# audio-amp-v1.net
KiCad netlist of a schematic drawn in EAGLE
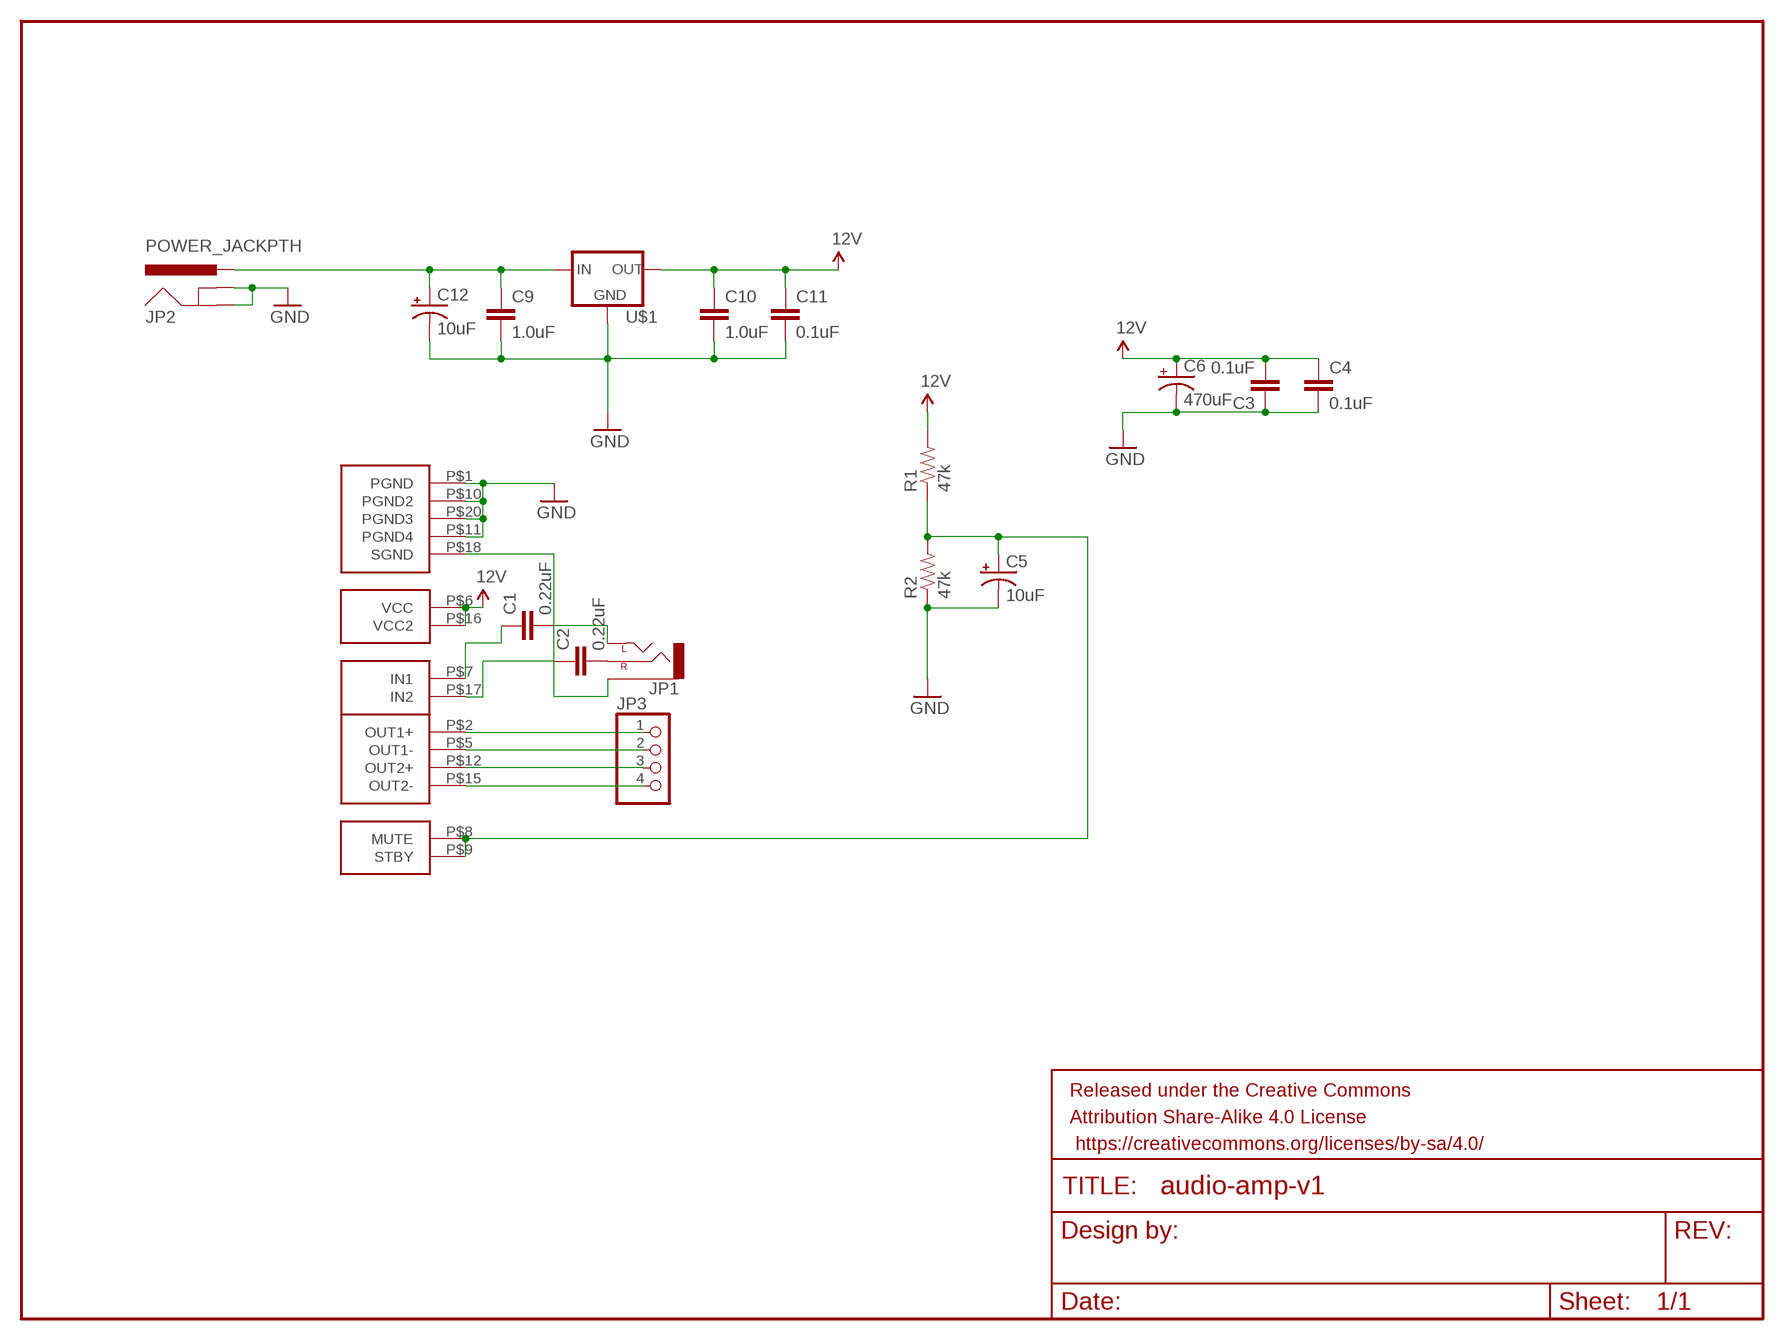
[diagram p0: schematic, sheet 1]

(export (version "E")
  (design (tool "Eeschema 10.0.6"))
  (components
    (comp (ref "C1")
      (value "0.22uF")
      (footprint "eagle-import:0603-CAP")
      (libsource (lib "eagle-import") (part "0.22UF-25V-10%(0603)"))
    )
    (comp (ref "C2")
      (value "0.22uF")
      (footprint "eagle-import:0603-CAP")
      (libsource (lib "eagle-import") (part "0.22UF-25V-10%(0603)"))
    )
    (comp (ref "C3")
      (value "0.1uF")
      (footprint "eagle-import:0603-CAP")
      (libsource (lib "eagle-import") (part "0.1UF-25V-5%(0603)"))
    )
    (comp (ref "C4")
      (value "0.1uF")
      (footprint "eagle-import:0603-CAP")
      (libsource (lib "eagle-import") (part "0.1UF-25V-5%(0603)"))
    )
    (comp (ref "C5")
      (value "10uF")
      (footprint "eagle-import:PANASONIC_C")
      (libsource (lib "eagle-import") (part "CAP_POLC"))
    )
    (comp (ref "C6")
      (value "470uF")
      (footprint "eagle-import:NIC_10X10.5_CAP")
      (libsource (lib "eagle-import") (part "100UF-63V-20%(ELECT)"))
    )
    (comp (ref "C9")
      (value "1.0uF")
      (footprint "eagle-import:0603-CAP")
      (libsource (lib "eagle-import") (part "1.0UF-16V-10%(0603)"))
    )
    (comp (ref "C10")
      (value "1.0uF")
      (footprint "eagle-import:0603-CAP")
      (libsource (lib "eagle-import") (part "1.0UF-16V-10%(0603)"))
    )
    (comp (ref "C11")
      (value "0.1uF")
      (footprint "eagle-import:0603-CAP")
      (libsource (lib "eagle-import") (part "1.0UF-16V-10%(0603)"))
    )
    (comp (ref "C12")
      (value "10uF")
      (footprint "eagle-import:PANASONIC_C")
      (libsource (lib "eagle-import") (part "CAP_POLC"))
    )
    (comp (ref "FRAME1")
      (value "FRAME-LETTERNO_PACKAGE")
      (footprint "eagle-import:DUMMY")
      (fields (field (name "DESIGNER") "Nobody"))
      (libsource (lib "eagle-import") (part "FRAME-LETTERNO_PACKAGE"))
    )
    (comp (ref "JP1")
      (value "AUDIO-JACKSMD2")
      (footprint "eagle-import:AUDIO-JACK-3.5MM-SMD")
      (libsource (lib "eagle-import") (part "AUDIO-JACKSMD2"))
    )
    (comp (ref "JP2")
      (value "POWER_JACKPTH")
      (footprint "eagle-import:POWER_JACK_PTH")
      (libsource (lib "eagle-import") (part "POWER_JACKPTH"))
    )
    (comp (ref "JP3")
      (value "PINHD-1X4")
      (footprint "eagle-import:1X04")
      (libsource (lib "eagle-import") (part "PINHD-1X4"))
    )
    (comp (ref "R1")
      (value "47k")
      (footprint "eagle-import:0603-RES")
      (libsource (lib "eagle-import") (part "RESISTOR0603-RES"))
    )
    (comp (ref "R2")
      (value "47k")
      (footprint "eagle-import:0603-RES")
      (libsource (lib "eagle-import") (part "RESISTOR0603-RES"))
    )
    (comp (ref "U$1")
      (value "V_REG_78XX-TO-220")
      (footprint "eagle-import:TO-220-ALT")
      (libsource (lib "eagle-import") (part "V_REG_78XX-TO-220"))
    )
    (comp (ref "U$2")
      (value "TDA7266D")
      (footprint "eagle-import:TDA7266D")
      (libsource (lib "eagle-import") (part "TDA7266D"))
    )
  )
  (nets
    (net (code "1") (name "12V") (class "Default")
      (node (ref "C10") (pin "1") (pinfunction "1_1") (pintype "passive"))
      (node (ref "C11") (pin "1") (pinfunction "1_1") (pintype "passive"))
      (node (ref "C3") (pin "2") (pinfunction "2_2") (pintype "passive"))
      (node (ref "C4") (pin "1") (pinfunction "1_1") (pintype "passive"))
      (node (ref "C6") (pin "+") (pinfunction "+_+") (pintype "passive"))
      (node (ref "R1") (pin "2") (pinfunction "2_2") (pintype "passive"))
      (node (ref "U$1") (pin "OUT") (pinfunction "OUT_OUT") (pintype "passive"))
      (node (ref "U$2") (pin "P$16") (pinfunction "VCC2_P$16") (pintype "bidirectional"))
      (node (ref "U$2") (pin "P$6") (pinfunction "VCC_P$6") (pintype "bidirectional"))
    )
    (net (code "2") (name "GND") (class "Default")
      (node (ref "C10") (pin "2") (pinfunction "2_2") (pintype "passive"))
      (node (ref "C11") (pin "2") (pinfunction "2_2") (pintype "passive"))
      (node (ref "C12") (pin "-") (pinfunction "-_-") (pintype "passive"))
      (node (ref "C3") (pin "1") (pinfunction "1_1") (pintype "passive"))
      (node (ref "C4") (pin "2") (pinfunction "2_2") (pintype "passive"))
      (node (ref "C5") (pin "-") (pinfunction "-_-") (pintype "passive"))
      (node (ref "C6") (pin "-") (pinfunction "-_-") (pintype "passive"))
      (node (ref "C9") (pin "2") (pinfunction "2_2") (pintype "passive"))
      (node (ref "JP2") (pin "GND") (pinfunction "GND_GND") (pintype "bidirectional"))
      (node (ref "JP2") (pin "GNDBREAK") (pinfunction "GNDBREAK_GNDBREAK") (pintype "bidirectional"))
      (node (ref "R2") (pin "1") (pinfunction "1_1") (pintype "passive"))
      (node (ref "U$1") (pin "GND") (pinfunction "GND_GND") (pintype "input"))
      (node (ref "U$2") (pin "P$1") (pinfunction "PGND_P$1") (pintype "bidirectional"))
      (node (ref "U$2") (pin "P$10") (pinfunction "PGND2_P$10") (pintype "bidirectional"))
      (node (ref "U$2") (pin "P$11") (pinfunction "PGND4_P$11") (pintype "bidirectional"))
      (node (ref "U$2") (pin "P$20") (pinfunction "PGND3_P$20") (pintype "bidirectional"))
    )
    (net (code "3") (name "Net-(C12-Pad+)") (class "Default")
      (node (ref "C12") (pin "+") (pinfunction "+_+") (pintype "passive"))
      (node (ref "C9") (pin "1") (pinfunction "1_1") (pintype "passive"))
      (node (ref "JP2") (pin "PWR") (pinfunction "PWR_PWR") (pintype "bidirectional"))
      (node (ref "U$1") (pin "IN") (pinfunction "IN_IN") (pintype "input"))
    )
    (net (code "4") (name "Net-(JP1-LEFT)") (class "Default")
      (node (ref "C1") (pin "2") (pinfunction "2_2") (pintype "passive"))
      (node (ref "JP1") (pin "TIP") (pinfunction "LEFT_TIP") (pintype "bidirectional"))
    )
    (net (code "5") (name "Net-(JP1-RIGHT)") (class "Default")
      (node (ref "C2") (pin "2") (pinfunction "2_2") (pintype "passive"))
      (node (ref "JP1") (pin "RING") (pinfunction "RIGHT_RING") (pintype "bidirectional"))
    )
    (net (code "6") (name "Net-(U$2-IN1)") (class "Default")
      (node (ref "C1") (pin "1") (pinfunction "1_1") (pintype "passive"))
      (node (ref "U$2") (pin "P$7") (pinfunction "IN1_P$7") (pintype "bidirectional"))
    )
    (net (code "7") (name "Net-(U$2-IN2)") (class "Default")
      (node (ref "C2") (pin "1") (pinfunction "1_1") (pintype "passive"))
      (node (ref "U$2") (pin "P$17") (pinfunction "IN2_P$17") (pintype "bidirectional"))
    )
    (net (code "8") (name "Net-(U$2-MUTE)") (class "Default")
      (node (ref "C5") (pin "+") (pinfunction "+_+") (pintype "passive"))
      (node (ref "R1") (pin "1") (pinfunction "1_1") (pintype "passive"))
      (node (ref "R2") (pin "2") (pinfunction "2_2") (pintype "passive"))
      (node (ref "U$2") (pin "P$8") (pinfunction "MUTE_P$8") (pintype "bidirectional"))
      (node (ref "U$2") (pin "P$9") (pinfunction "STBY_P$9") (pintype "bidirectional"))
    )
    (net (code "9") (name "Net-(U$2-OUT1+)") (class "Default")
      (node (ref "JP3") (pin "1") (pinfunction "1_1") (pintype "passive"))
      (node (ref "U$2") (pin "P$2") (pinfunction "OUT1+_P$2") (pintype "bidirectional"))
    )
    (net (code "10") (name "Net-(U$2-OUT1-)") (class "Default")
      (node (ref "JP3") (pin "2") (pinfunction "2_2") (pintype "passive"))
      (node (ref "U$2") (pin "P$5") (pinfunction "OUT1-_P$5") (pintype "bidirectional"))
    )
    (net (code "11") (name "Net-(U$2-OUT2+)") (class "Default")
      (node (ref "JP3") (pin "3") (pinfunction "3_3") (pintype "passive"))
      (node (ref "U$2") (pin "P$12") (pinfunction "OUT2+_P$12") (pintype "bidirectional"))
    )
    (net (code "12") (name "Net-(U$2-OUT2-)") (class "Default")
      (node (ref "JP3") (pin "4") (pinfunction "4_4") (pintype "passive"))
      (node (ref "U$2") (pin "P$15") (pinfunction "OUT2-_P$15") (pintype "bidirectional"))
    )
    (net (code "13") (name "Net-(U$2-SGND)") (class "Default")
      (node (ref "JP1") (pin "SLEEVE") (pinfunction "SLEEVE_SLEEVE") (pintype "bidirectional"))
      (node (ref "U$2") (pin "P$18") (pinfunction "SGND_P$18") (pintype "bidirectional"))
    )
  )
)
